# schematic.net
KiCad netlist of a schematic drawn in EasyEDA
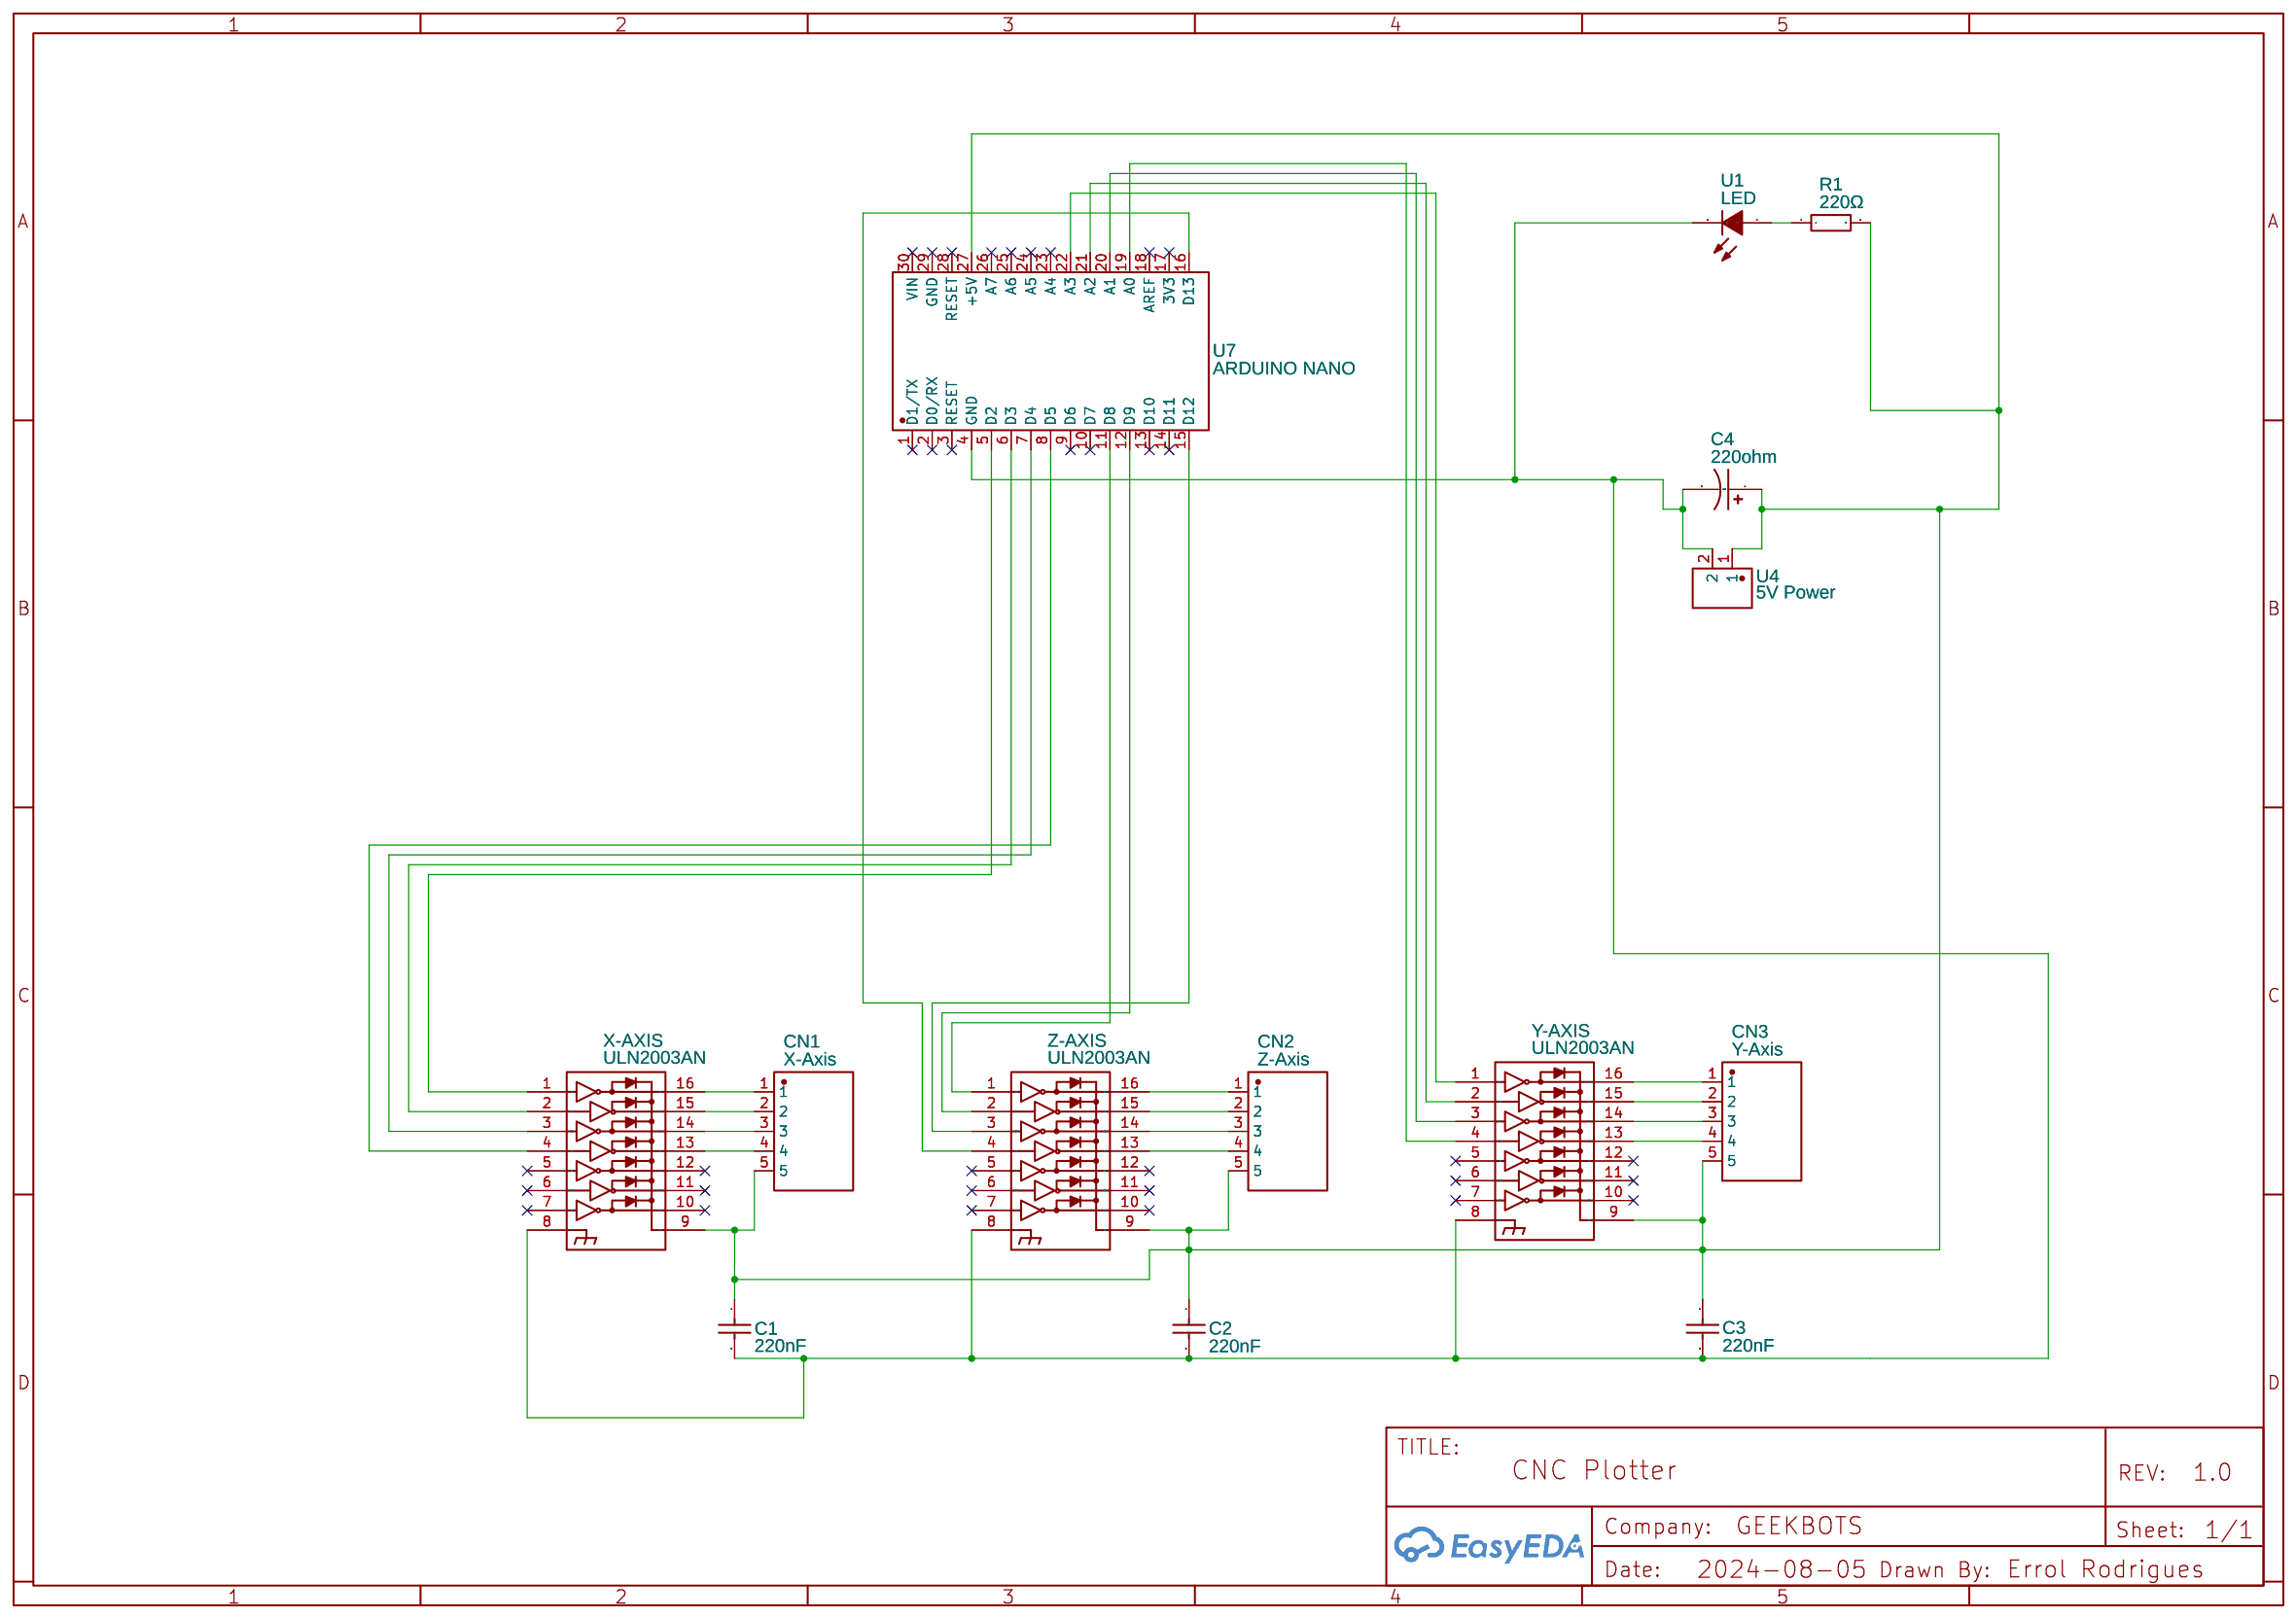
[diagram p0: schematic sheet]

(export (version "E")
  (design (tool "Eeschema 10.0.6"))
  (components
    (comp (ref "C1")
      (value "220nF")
      (fields
        (field (name "Manufacturer Part") "CD1H224KC9BER1E000")
        (field (name "Manufacturer") "Dersonic(德尔创)")
      )
      (libsource (lib "") (part "CD1H224KC9BER1E000"))
    )
    (comp (ref "C2")
      (value "220nF")
      (fields
        (field (name "Manufacturer Part") "CD1H224KC9BER1E000")
        (field (name "Manufacturer") "Dersonic(德尔创)")
      )
      (libsource (lib "") (part "CD1H224KC9BER1E000"))
    )
    (comp (ref "C3")
      (value "220nF")
      (fields
        (field (name "Manufacturer Part") "CD1H224KC9BER1E000")
        (field (name "Manufacturer") "Dersonic(德尔创)")
      )
      (libsource (lib "") (part "CD1H224KC9BER1E000"))
    )
    (comp (ref "C4")
      (value "220ohm")
      (fields
        (field (name "Manufacturer Part") "226BPS035M")
        (field (name "Manufacturer") "Illinois Capacitor")
      )
      (libsource (lib "") (part "226BPS035M"))
    )
    (comp (ref "CN1")
      (value "X-Axis")
      (fields (field (name "Manufacturer Part") "B5B-XH-A(LF)(SN)") (field (name "Manufacturer") "JST"))
      (libsource (lib "") (part "B5B-XH-A (LF)(SN)"))
    )
    (comp (ref "CN2")
      (value "Z-Axis")
      (fields (field (name "Manufacturer Part") "B5B-XH-A(LF)(SN)") (field (name "Manufacturer") "JST"))
      (libsource (lib "") (part "B5B-XH-A (LF)(SN)"))
    )
    (comp (ref "CN3")
      (value "Y-Axis")
      (fields (field (name "Manufacturer Part") "B5B-XH-A(LF)(SN)") (field (name "Manufacturer") "JST"))
      (libsource (lib "") (part "B5B-XH-A (LF)(SN)"))
    )
    (comp (ref "R1")
      (value "220Ω")
      (fields
        (field (name "Manufacturer Part") "MF1/4W-300KΩ±1% T")
        (field (name "Manufacturer") "CCO(千志电子)")
      )
      (libsource (lib "") (part "MF1/4W-300KΩ±1% T52"))
    )
    (comp (ref "U1")
      (value "LED")
      (fields
        (field (name "Manufacturer Part") "IR333C-A(BY)(N)")
        (field (name "Manufacturer") "EVERLIGHT(亿光)")
      )
      (libsource (lib "") (part "IR333C-A(BY)(N)"))
    )
    (comp (ref "U4")
      (value "5V Power")
      (fields
        (field (name "Manufacturer Part") "XY126V-5.0-2P")
        (field (name "Manufacturer") "XINLAIYA(新莱亚)")
      )
      (libsource (lib "") (part "XY126V-5.0-2P"))
    )
    (comp (ref "U7")
      (value "ARDUINO NANO")
      (fields (field (name "Manufacturer Part") "ARDUINO_NANO"))
      (libsource (lib "") (part "ARDUINO_NANO"))
    )
    (comp (ref "X-AXIS")
      (value "ULN2003AN")
      (fields (field (name "Manufacturer") "TI(德州仪器)"))
      (libsource (lib "") (part "ULN2003AN"))
    )
    (comp (ref "Y-AXIS")
      (value "ULN2003AN")
      (fields (field (name "Manufacturer") "TI(德州仪器)"))
      (libsource (lib "") (part "ULN2003AN_1"))
    )
    (comp (ref "Z-AXIS")
      (value "ULN2003AN")
      (fields (field (name "Manufacturer") "TI(德州仪器)"))
      (libsource (lib "") (part "ULN2003AN_2"))
    )
  )
  (nets
    (net (code "1") (name "Net-(U1-A)") (class "Default")
      (node (ref "R1") (pin "1") (pinfunction "1_1") (pintype "unspecified"))
      (node (ref "U1") (pin "1") (pinfunction "A_1") (pintype "input"))
    )
    (net (code "2") (name "Net-(U1-C)") (class "Default")
      (node (ref "C1") (pin "2") (pinfunction "2_2") (pintype "input"))
      (node (ref "C2") (pin "2") (pinfunction "2_2") (pintype "input"))
      (node (ref "C3") (pin "2") (pinfunction "2_2") (pintype "input"))
      (node (ref "C4") (pin "2") (pinfunction "2_2") (pintype "unspecified"))
      (node (ref "U1") (pin "2") (pinfunction "C_2") (pintype "input"))
      (node (ref "U4") (pin "2") (pinfunction "2_2") (pintype "unspecified"))
      (node (ref "U7") (pin "4") (pinfunction "GND_4") (pintype "unspecified"))
      (node (ref "X-AXIS") (pin "8") (pinfunction "E_8") (pintype "unspecified"))
      (node (ref "Y-AXIS") (pin "8") (pinfunction "E_8") (pintype "unspecified"))
      (node (ref "Z-AXIS") (pin "8") (pinfunction "E_8") (pintype "unspecified"))
    )
    (net (code "3") (name "Net-(U7-+5V)") (class "Default")
      (node (ref "C1") (pin "1") (pinfunction "1_1") (pintype "input"))
      (node (ref "C2") (pin "1") (pinfunction "1_1") (pintype "input"))
      (node (ref "C3") (pin "1") (pinfunction "1_1") (pintype "input"))
      (node (ref "C4") (pin "1") (pinfunction "1_1") (pintype "unspecified"))
      (node (ref "CN1") (pin "5") (pinfunction "5_5") (pintype "unspecified"))
      (node (ref "CN2") (pin "5") (pinfunction "5_5") (pintype "unspecified"))
      (node (ref "CN3") (pin "5") (pinfunction "5_5") (pintype "unspecified"))
      (node (ref "R1") (pin "2") (pinfunction "2_2") (pintype "unspecified"))
      (node (ref "U4") (pin "1") (pinfunction "1_1") (pintype "unspecified"))
      (node (ref "U7") (pin "27") (pinfunction "+5V_27") (pintype "unspecified"))
      (node (ref "X-AXIS") (pin "9") (pinfunction "COM_9") (pintype "unspecified"))
      (node (ref "Y-AXIS") (pin "9") (pinfunction "COM_9") (pintype "unspecified"))
      (node (ref "Z-AXIS") (pin "9") (pinfunction "COM_9") (pintype "unspecified"))
    )
    (net (code "4") (name "Net-(U7-A0)") (class "Default")
      (node (ref "U7") (pin "19") (pinfunction "A0_19") (pintype "unspecified"))
      (node (ref "Y-AXIS") (pin "4") (pinfunction "4B_4") (pintype "unspecified"))
    )
    (net (code "5") (name "Net-(U7-A1)") (class "Default")
      (node (ref "U7") (pin "20") (pinfunction "A1_20") (pintype "unspecified"))
      (node (ref "Y-AXIS") (pin "3") (pinfunction "3B_3") (pintype "unspecified"))
    )
    (net (code "6") (name "Net-(U7-A2)") (class "Default")
      (node (ref "U7") (pin "21") (pinfunction "A2_21") (pintype "unspecified"))
      (node (ref "Y-AXIS") (pin "2") (pinfunction "2B_2") (pintype "unspecified"))
    )
    (net (code "7") (name "Net-(U7-A3)") (class "Default")
      (node (ref "U7") (pin "22") (pinfunction "A3_22") (pintype "unspecified"))
      (node (ref "Y-AXIS") (pin "1") (pinfunction "1B_1") (pintype "unspecified"))
    )
    (net (code "8") (name "Net-(U7-D2)") (class "Default")
      (node (ref "U7") (pin "5") (pinfunction "D2_5") (pintype "unspecified"))
      (node (ref "X-AXIS") (pin "1") (pinfunction "1B_1") (pintype "unspecified"))
    )
    (net (code "9") (name "Net-(U7-D3)") (class "Default")
      (node (ref "U7") (pin "6") (pinfunction "D3_6") (pintype "unspecified"))
      (node (ref "X-AXIS") (pin "2") (pinfunction "2B_2") (pintype "unspecified"))
    )
    (net (code "10") (name "Net-(U7-D4)") (class "Default")
      (node (ref "U7") (pin "7") (pinfunction "D4_7") (pintype "unspecified"))
      (node (ref "X-AXIS") (pin "3") (pinfunction "3B_3") (pintype "unspecified"))
    )
    (net (code "11") (name "Net-(U7-D5)") (class "Default")
      (node (ref "U7") (pin "8") (pinfunction "D5_8") (pintype "unspecified"))
      (node (ref "X-AXIS") (pin "4") (pinfunction "4B_4") (pintype "unspecified"))
    )
    (net (code "12") (name "Net-(U7-D8)") (class "Default")
      (node (ref "U7") (pin "11") (pinfunction "D8_11") (pintype "unspecified"))
      (node (ref "Z-AXIS") (pin "1") (pinfunction "1B_1") (pintype "unspecified"))
    )
    (net (code "13") (name "Net-(U7-D9)") (class "Default")
      (node (ref "U7") (pin "12") (pinfunction "D9_12") (pintype "unspecified"))
      (node (ref "Z-AXIS") (pin "2") (pinfunction "2B_2") (pintype "unspecified"))
    )
    (net (code "14") (name "Net-(U7-D12)") (class "Default")
      (node (ref "U7") (pin "15") (pinfunction "D12_15") (pintype "unspecified"))
      (node (ref "Z-AXIS") (pin "3") (pinfunction "3B_3") (pintype "unspecified"))
    )
    (net (code "15") (name "Net-(U7-D13)") (class "Default")
      (node (ref "U7") (pin "16") (pinfunction "D13_16") (pintype "unspecified"))
      (node (ref "Z-AXIS") (pin "4") (pinfunction "4B_4") (pintype "unspecified"))
    )
    (net (code "16") (name "Net-(X-AXIS-1C)") (class "Default")
      (node (ref "CN1") (pin "1") (pinfunction "1_1") (pintype "unspecified"))
      (node (ref "X-AXIS") (pin "16") (pinfunction "1C_16") (pintype "unspecified"))
    )
    (net (code "17") (name "Net-(X-AXIS-2C)") (class "Default")
      (node (ref "CN1") (pin "2") (pinfunction "2_2") (pintype "unspecified"))
      (node (ref "X-AXIS") (pin "15") (pinfunction "2C_15") (pintype "unspecified"))
    )
    (net (code "18") (name "Net-(X-AXIS-3C)") (class "Default")
      (node (ref "CN1") (pin "3") (pinfunction "3_3") (pintype "unspecified"))
      (node (ref "X-AXIS") (pin "14") (pinfunction "3C_14") (pintype "unspecified"))
    )
    (net (code "19") (name "Net-(X-AXIS-4C)") (class "Default")
      (node (ref "CN1") (pin "4") (pinfunction "4_4") (pintype "unspecified"))
      (node (ref "X-AXIS") (pin "13") (pinfunction "4C_13") (pintype "unspecified"))
    )
    (net (code "20") (name "Net-(Y-AXIS-1C)") (class "Default")
      (node (ref "CN3") (pin "1") (pinfunction "1_1") (pintype "unspecified"))
      (node (ref "Y-AXIS") (pin "16") (pinfunction "1C_16") (pintype "unspecified"))
    )
    (net (code "21") (name "Net-(Y-AXIS-2C)") (class "Default")
      (node (ref "CN3") (pin "2") (pinfunction "2_2") (pintype "unspecified"))
      (node (ref "Y-AXIS") (pin "15") (pinfunction "2C_15") (pintype "unspecified"))
    )
    (net (code "22") (name "Net-(Y-AXIS-3C)") (class "Default")
      (node (ref "CN3") (pin "3") (pinfunction "3_3") (pintype "unspecified"))
      (node (ref "Y-AXIS") (pin "14") (pinfunction "3C_14") (pintype "unspecified"))
    )
    (net (code "23") (name "Net-(Y-AXIS-4C)") (class "Default")
      (node (ref "CN3") (pin "4") (pinfunction "4_4") (pintype "unspecified"))
      (node (ref "Y-AXIS") (pin "13") (pinfunction "4C_13") (pintype "unspecified"))
    )
    (net (code "24") (name "Net-(Z-AXIS-1C)") (class "Default")
      (node (ref "CN2") (pin "1") (pinfunction "1_1") (pintype "unspecified"))
      (node (ref "Z-AXIS") (pin "16") (pinfunction "1C_16") (pintype "unspecified"))
    )
    (net (code "25") (name "Net-(Z-AXIS-2C)") (class "Default")
      (node (ref "CN2") (pin "2") (pinfunction "2_2") (pintype "unspecified"))
      (node (ref "Z-AXIS") (pin "15") (pinfunction "2C_15") (pintype "unspecified"))
    )
    (net (code "26") (name "Net-(Z-AXIS-3C)") (class "Default")
      (node (ref "CN2") (pin "3") (pinfunction "3_3") (pintype "unspecified"))
      (node (ref "Z-AXIS") (pin "14") (pinfunction "3C_14") (pintype "unspecified"))
    )
    (net (code "27") (name "Net-(Z-AXIS-4C)") (class "Default")
      (node (ref "CN2") (pin "4") (pinfunction "4_4") (pintype "unspecified"))
      (node (ref "Z-AXIS") (pin "13") (pinfunction "4C_13") (pintype "unspecified"))
    )
    (net (code "28") (name "unconnected-(U7-3V3-Pad17)") (class "Default")
      (node (ref "U7") (pin "17") (pinfunction "3V3_17") (pintype "unspecified+no_connect"))
    )
    (net (code "29") (name "unconnected-(U7-A4-Pad23)") (class "Default")
      (node (ref "U7") (pin "23") (pinfunction "A4_23") (pintype "unspecified+no_connect"))
    )
    (net (code "30") (name "unconnected-(U7-A5-Pad24)") (class "Default")
      (node (ref "U7") (pin "24") (pinfunction "A5_24") (pintype "unspecified+no_connect"))
    )
    (net (code "31") (name "unconnected-(U7-A6-Pad25)") (class "Default")
      (node (ref "U7") (pin "25") (pinfunction "A6_25") (pintype "unspecified+no_connect"))
    )
    (net (code "32") (name "unconnected-(U7-A7-Pad26)") (class "Default")
      (node (ref "U7") (pin "26") (pinfunction "A7_26") (pintype "unspecified+no_connect"))
    )
    (net (code "33") (name "unconnected-(U7-AREF-Pad18)") (class "Default")
      (node (ref "U7") (pin "18") (pinfunction "AREF_18") (pintype "unspecified+no_connect"))
    )
    (net (code "34") (name "unconnected-(U7-D0{slash}RX-Pad2)") (class "Default")
      (node (ref "U7") (pin "2") (pinfunction "D0/RX_2") (pintype "unspecified+no_connect"))
    )
    (net (code "35") (name "unconnected-(U7-D1{slash}TX-Pad1)") (class "Default")
      (node (ref "U7") (pin "1") (pinfunction "D1/TX_1") (pintype "unspecified+no_connect"))
    )
    (net (code "36") (name "unconnected-(U7-D6-Pad9)") (class "Default")
      (node (ref "U7") (pin "9") (pinfunction "D6_9") (pintype "unspecified+no_connect"))
    )
    (net (code "37") (name "unconnected-(U7-D7-Pad10)") (class "Default")
      (node (ref "U7") (pin "10") (pinfunction "D7_10") (pintype "unspecified+no_connect"))
    )
    (net (code "38") (name "unconnected-(U7-D10-Pad13)") (class "Default")
      (node (ref "U7") (pin "13") (pinfunction "D10_13") (pintype "unspecified+no_connect"))
    )
    (net (code "39") (name "unconnected-(U7-D11-Pad14)") (class "Default")
      (node (ref "U7") (pin "14") (pinfunction "D11_14") (pintype "unspecified+no_connect"))
    )
    (net (code "40") (name "unconnected-(U7-GND-Pad29)") (class "Default")
      (node (ref "U7") (pin "29") (pinfunction "GND_29") (pintype "unspecified+no_connect"))
    )
    (net (code "41") (name "unconnected-(U7-RESET-Pad3)") (class "Default")
      (node (ref "U7") (pin "3") (pinfunction "RESET_3") (pintype "unspecified+no_connect"))
    )
    (net (code "42") (name "unconnected-(U7-RESET-Pad28)") (class "Default")
      (node (ref "U7") (pin "28") (pinfunction "RESET_28") (pintype "unspecified+no_connect"))
    )
    (net (code "43") (name "unconnected-(U7-VIN-Pad30)") (class "Default")
      (node (ref "U7") (pin "30") (pinfunction "VIN_30") (pintype "unspecified+no_connect"))
    )
    (net (code "44") (name "unconnected-(X-AXIS-5B-Pad5)") (class "Default")
      (node (ref "X-AXIS") (pin "5") (pinfunction "5B_5") (pintype "unspecified+no_connect"))
    )
    (net (code "45") (name "unconnected-(X-AXIS-5C-Pad12)") (class "Default")
      (node (ref "X-AXIS") (pin "12") (pinfunction "5C_12") (pintype "unspecified+no_connect"))
    )
    (net (code "46") (name "unconnected-(X-AXIS-6B-Pad6)") (class "Default")
      (node (ref "X-AXIS") (pin "6") (pinfunction "6B_6") (pintype "unspecified+no_connect"))
    )
    (net (code "47") (name "unconnected-(X-AXIS-6C-Pad11)") (class "Default")
      (node (ref "X-AXIS") (pin "11") (pinfunction "6C_11") (pintype "unspecified+no_connect"))
    )
    (net (code "48") (name "unconnected-(X-AXIS-7B-Pad7)") (class "Default")
      (node (ref "X-AXIS") (pin "7") (pinfunction "7B_7") (pintype "unspecified+no_connect"))
    )
    (net (code "49") (name "unconnected-(X-AXIS-7C-Pad10)") (class "Default")
      (node (ref "X-AXIS") (pin "10") (pinfunction "7C_10") (pintype "unspecified+no_connect"))
    )
    (net (code "50") (name "unconnected-(Y-AXIS-5B-Pad5)") (class "Default")
      (node (ref "Y-AXIS") (pin "5") (pinfunction "5B_5") (pintype "unspecified+no_connect"))
    )
    (net (code "51") (name "unconnected-(Y-AXIS-5C-Pad12)") (class "Default")
      (node (ref "Y-AXIS") (pin "12") (pinfunction "5C_12") (pintype "unspecified+no_connect"))
    )
    (net (code "52") (name "unconnected-(Y-AXIS-6B-Pad6)") (class "Default")
      (node (ref "Y-AXIS") (pin "6") (pinfunction "6B_6") (pintype "unspecified+no_connect"))
    )
    (net (code "53") (name "unconnected-(Y-AXIS-6C-Pad11)") (class "Default")
      (node (ref "Y-AXIS") (pin "11") (pinfunction "6C_11") (pintype "unspecified+no_connect"))
    )
    (net (code "54") (name "unconnected-(Y-AXIS-7B-Pad7)") (class "Default")
      (node (ref "Y-AXIS") (pin "7") (pinfunction "7B_7") (pintype "unspecified+no_connect"))
    )
    (net (code "55") (name "unconnected-(Y-AXIS-7C-Pad10)") (class "Default")
      (node (ref "Y-AXIS") (pin "10") (pinfunction "7C_10") (pintype "unspecified+no_connect"))
    )
    (net (code "56") (name "unconnected-(Z-AXIS-5B-Pad5)") (class "Default")
      (node (ref "Z-AXIS") (pin "5") (pinfunction "5B_5") (pintype "unspecified+no_connect"))
    )
    (net (code "57") (name "unconnected-(Z-AXIS-5C-Pad12)") (class "Default")
      (node (ref "Z-AXIS") (pin "12") (pinfunction "5C_12") (pintype "unspecified+no_connect"))
    )
    (net (code "58") (name "unconnected-(Z-AXIS-6B-Pad6)") (class "Default")
      (node (ref "Z-AXIS") (pin "6") (pinfunction "6B_6") (pintype "unspecified+no_connect"))
    )
    (net (code "59") (name "unconnected-(Z-AXIS-6C-Pad11)") (class "Default")
      (node (ref "Z-AXIS") (pin "11") (pinfunction "6C_11") (pintype "unspecified+no_connect"))
    )
    (net (code "60") (name "unconnected-(Z-AXIS-7B-Pad7)") (class "Default")
      (node (ref "Z-AXIS") (pin "7") (pinfunction "7B_7") (pintype "unspecified+no_connect"))
    )
    (net (code "61") (name "unconnected-(Z-AXIS-7C-Pad10)") (class "Default")
      (node (ref "Z-AXIS") (pin "10") (pinfunction "7C_10") (pintype "unspecified+no_connect"))
    )
  )
)
